# isolation.net
KiCad netlist of a schematic drawn in Altium Designer
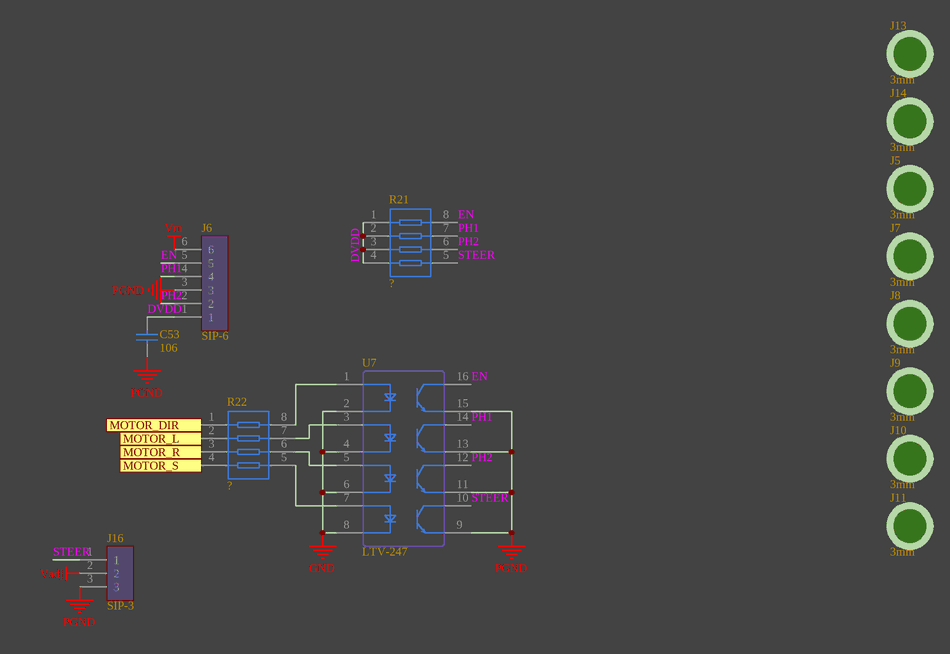
[diagram p0: isolation.SchDoc]

(export (version "E")
  (design (tool "Eeschema 10.0.6"))
  (components
    (comp (ref "C53")
      (value "106")
      (footprint "C0603")
      (description "Capacitor")
      (fields (field (name "PUBLISHER") "Altium Limited"))
      (libsource (lib "iMag") (part "电容"))
    )
    (comp (ref "J5") (value "3mm") (footprint "定位孔 3mm") (libsource (lib "iMag") (part "定位孔")))
    (comp (ref "J6") (value "SIP-6") (footprint "PH2.0-6P") (libsource (lib "iMag") (part "SIP-6")))
    (comp (ref "J7") (value "3mm") (footprint "定位孔 3mm") (libsource (lib "iMag") (part "定位孔")))
    (comp (ref "J8") (value "3mm") (footprint "定位孔 3mm") (libsource (lib "iMag") (part "定位孔")))
    (comp (ref "J9") (value "3mm") (footprint "定位孔 3mm") (libsource (lib "iMag") (part "定位孔")))
    (comp (ref "J10") (value "3mm") (footprint "定位孔 3mm") (libsource (lib "iMag") (part "定位孔")))
    (comp (ref "J11") (value "3mm") (footprint "定位孔 3mm") (libsource (lib "iMag") (part "定位孔")))
    (comp (ref "J13") (value "3mm") (footprint "定位孔 3mm") (libsource (lib "iMag") (part "定位孔")))
    (comp (ref "J14") (value "3mm") (footprint "定位孔 3mm") (libsource (lib "iMag") (part "定位孔")))
    (comp (ref "J16") (value "SIP-3") (footprint "2.54排针1X3") (libsource (lib "iMag") (part "SIP-3")))
    (comp (ref "R21")
      (value "?")
      (footprint "0603_Rx4")
      (description "贴片排阻")
      (libsource (lib "iMag") (part "贴片排阻*4"))
    )
    (comp (ref "R22")
      (value "?")
      (footprint "0603_Rx4")
      (description "贴片排阻")
      (libsource (lib "iMag") (part "贴片排阻*4"))
    )
    (comp (ref "U7")
      (value "LTV-247")
      (footprint "WSOP-16")
      (fields (field (name "BOM_SUPPLIER PART") "C115451") (field (name "CONTRIBUTOR") "LCSC"))
      (libsource (lib "iMag") (part "4光耦"))
    )
  )
  (nets
    (net (code "1") (name "/DVDD") (class "Default")
      (node (ref "C53") (pin "2") (pinfunction "2_2") (pintype "passive"))
      (node (ref "J6") (pin "1") (pinfunction "1_1") (pintype "passive"))
      (node (ref "R21") (pin "1") (pinfunction "1_1") (pintype "passive"))
      (node (ref "R21") (pin "2") (pinfunction "2_2") (pintype "passive"))
      (node (ref "R21") (pin "3") (pinfunction "3_3") (pintype "passive"))
      (node (ref "R21") (pin "4") (pinfunction "4_4") (pintype "passive"))
    )
    (net (code "2") (name "/EN") (class "Default")
      (node (ref "J6") (pin "5") (pinfunction "5_5") (pintype "passive"))
      (node (ref "R21") (pin "8") (pinfunction "8_8") (pintype "passive"))
      (node (ref "U7") (pin "16") (pinfunction "COL1_16") (pintype "passive"))
    )
    (net (code "3") (name "/MOTOR_DIR") (class "Default")
      (node (ref "R22") (pin "1") (pinfunction "1_1") (pintype "passive"))
    )
    (net (code "4") (name "/MOTOR_L") (class "Default")
      (node (ref "R22") (pin "2") (pinfunction "2_2") (pintype "passive"))
    )
    (net (code "5") (name "/MOTOR_R") (class "Default")
      (node (ref "R22") (pin "3") (pinfunction "3_3") (pintype "passive"))
    )
    (net (code "6") (name "/MOTOR_S") (class "Default")
      (node (ref "R22") (pin "4") (pinfunction "4_4") (pintype "passive"))
    )
    (net (code "7") (name "/PH1") (class "Default")
      (node (ref "J6") (pin "4") (pinfunction "4_4") (pintype "passive"))
      (node (ref "R21") (pin "7") (pinfunction "7_7") (pintype "passive"))
      (node (ref "U7") (pin "14") (pinfunction "COL2_14") (pintype "passive"))
    )
    (net (code "8") (name "/PH2") (class "Default")
      (node (ref "J6") (pin "2") (pinfunction "2_2") (pintype "passive"))
      (node (ref "R21") (pin "6") (pinfunction "6_6") (pintype "passive"))
      (node (ref "U7") (pin "12") (pinfunction "COL3_12") (pintype "passive"))
    )
    (net (code "9") (name "/STEER") (class "Default")
      (node (ref "J16") (pin "1") (pinfunction "1_1") (pintype "passive"))
      (node (ref "R21") (pin "5") (pinfunction "5_5") (pintype "passive"))
      (node (ref "U7") (pin "10") (pinfunction "COL4_10") (pintype "passive"))
    )
    (net (code "10") (name "GND") (class "Default")
      (node (ref "U7") (pin "2") (pinfunction "CAT1_2") (pintype "passive"))
      (node (ref "U7") (pin "4") (pinfunction "CAT2_4") (pintype "passive"))
      (node (ref "U7") (pin "6") (pinfunction "CAT3_6") (pintype "passive"))
      (node (ref "U7") (pin "8") (pinfunction "CAT4_8") (pintype "passive"))
    )
    (net (code "11") (name "Net-(U7-AN1)") (class "Default")
      (node (ref "R22") (pin "8") (pinfunction "8_8") (pintype "passive"))
      (node (ref "U7") (pin "1") (pinfunction "AN1_1") (pintype "passive"))
    )
    (net (code "12") (name "Net-(U7-AN2)") (class "Default")
      (node (ref "R22") (pin "7") (pinfunction "7_7") (pintype "passive"))
      (node (ref "U7") (pin "3") (pinfunction "AN2_3") (pintype "passive"))
    )
    (net (code "13") (name "Net-(U7-AN3)") (class "Default")
      (node (ref "R22") (pin "6") (pinfunction "6_6") (pintype "passive"))
      (node (ref "U7") (pin "5") (pinfunction "AN3_5") (pintype "passive"))
    )
    (net (code "14") (name "Net-(U7-AN4)") (class "Default")
      (node (ref "R22") (pin "5") (pinfunction "5_5") (pintype "passive"))
      (node (ref "U7") (pin "7") (pinfunction "AN4_7") (pintype "passive"))
    )
    (net (code "15") (name "PGND") (class "Default")
      (node (ref "C53") (pin "1") (pinfunction "1_1") (pintype "passive"))
      (node (ref "J16") (pin "3") (pinfunction "3_3") (pintype "passive"))
      (node (ref "J6") (pin "3") (pinfunction "3_3") (pintype "passive"))
      (node (ref "U7") (pin "11") (pinfunction "EM3_11") (pintype "passive"))
      (node (ref "U7") (pin "13") (pinfunction "EM2_13") (pintype "passive"))
      (node (ref "U7") (pin "15") (pinfunction "EM1_15") (pintype "passive"))
      (node (ref "U7") (pin "9") (pinfunction "EM4_9") (pintype "passive"))
    )
    (net (code "16") (name "Vadj") (class "Default")
      (node (ref "J16") (pin "2") (pinfunction "2_2") (pintype "passive"))
    )
    (net (code "17") (name "Vm") (class "Default")
      (node (ref "J6") (pin "6") (pinfunction "6_6") (pintype "passive"))
    )
  )
)
